# ICEDevice.net
KiCad netlist of a schematic drawn in EAGLE
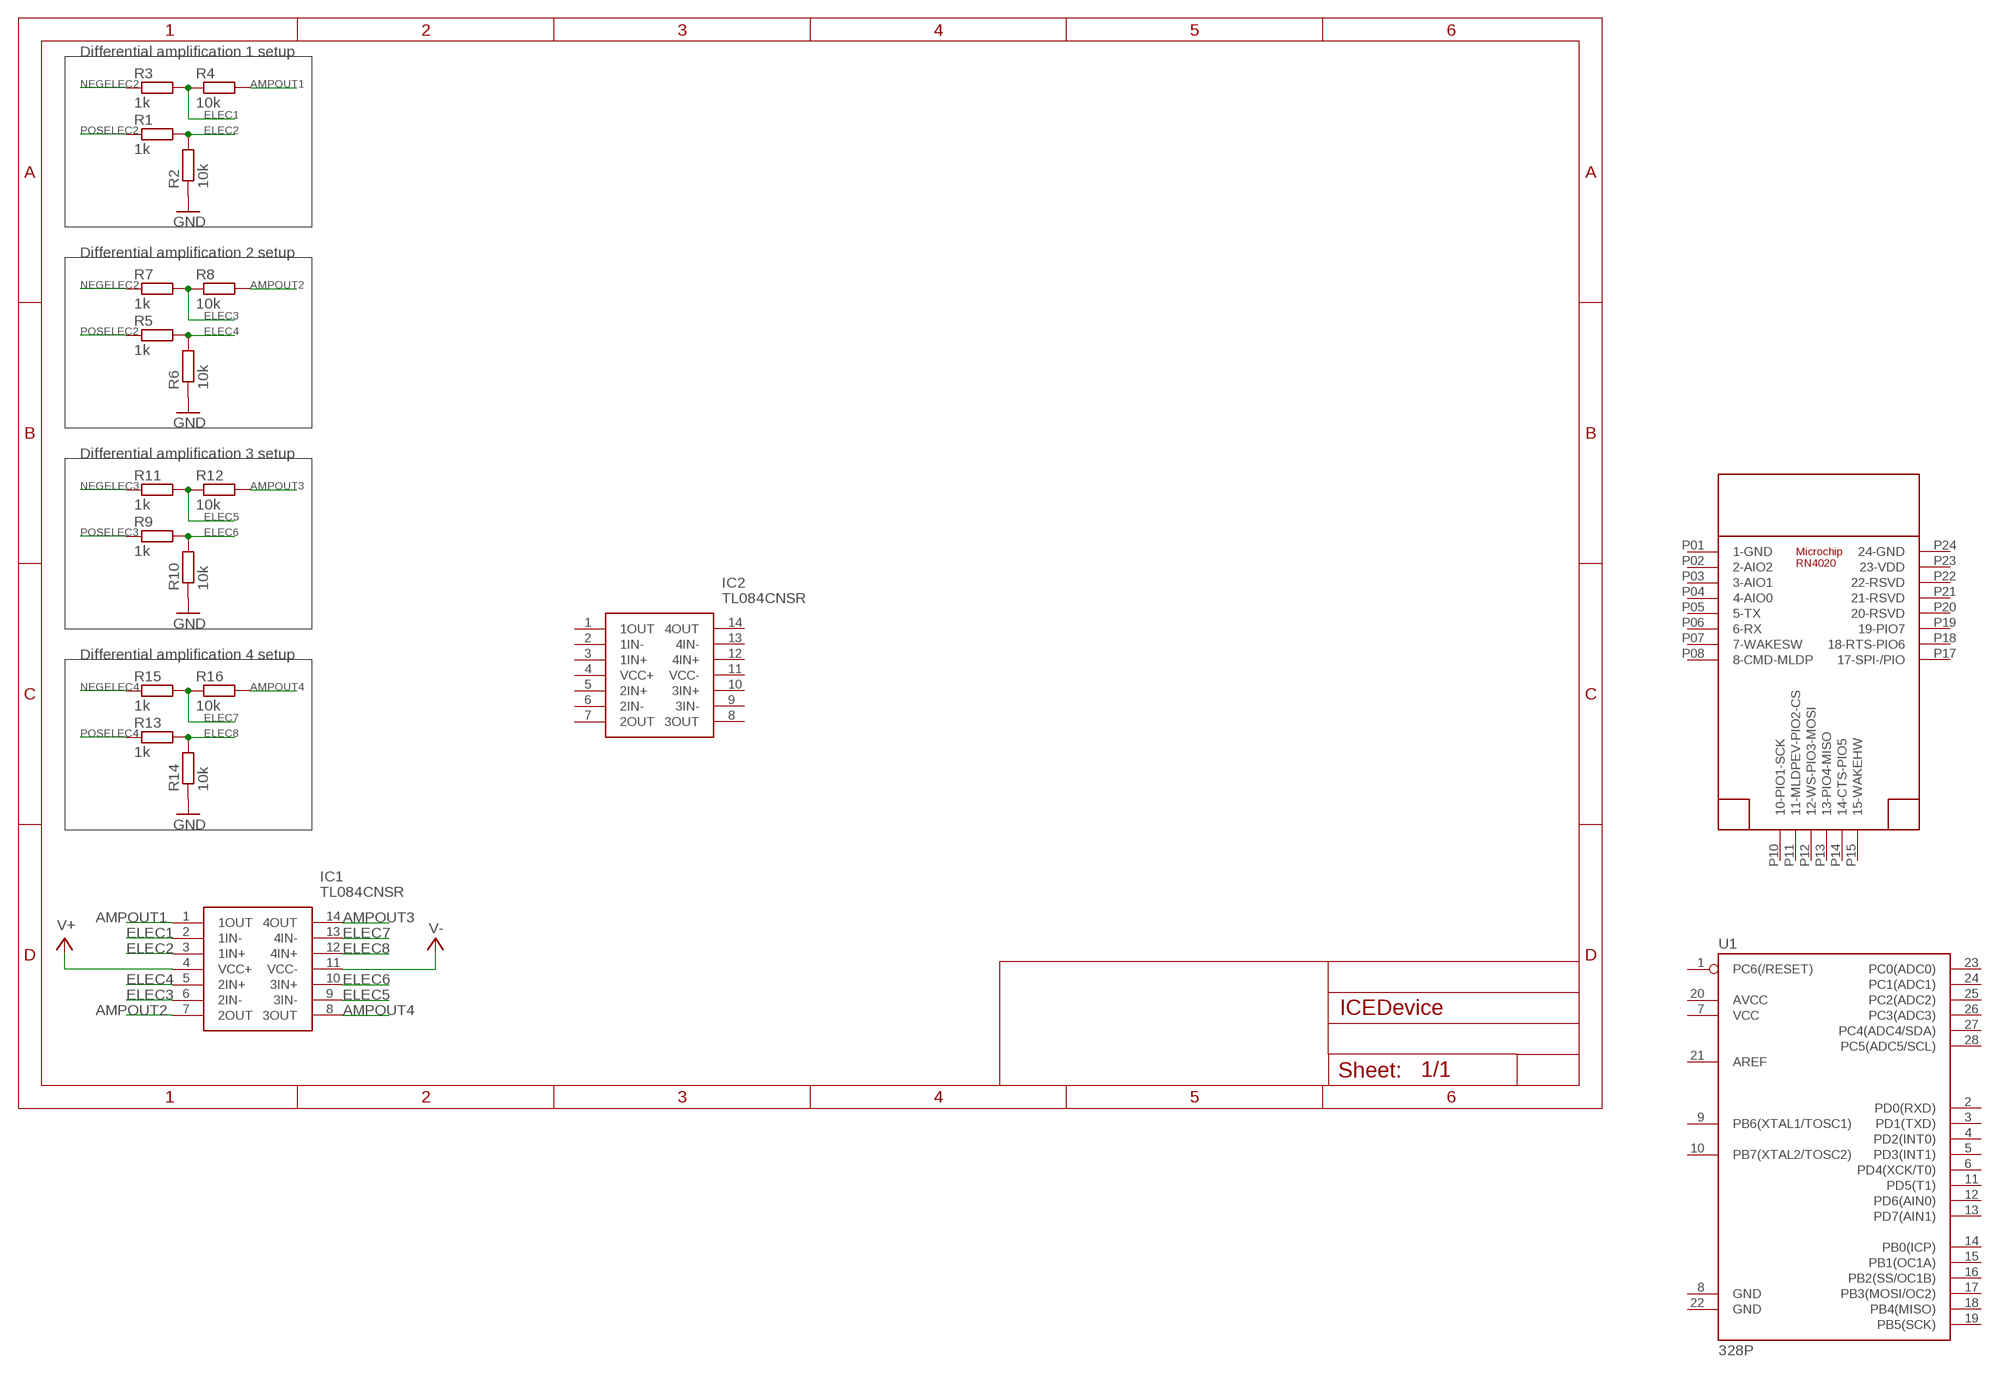
[diagram p0: schematic, sheet 1]

(export (version "E")
  (design (tool "Eeschema 10.0.6"))
  (components
    (comp (ref "IC1")
      (value "TL084CNSR")
      (footprint "eagle-import:SOIC127P780X200-14N")
      (fields (field (name "RS_PART_NUMBER") "1626742"))
      (libsource (lib "eagle-import") (part "TL084CNSR"))
    )
    (comp (ref "IC2")
      (value "TL084CNSR")
      (footprint "eagle-import:SOIC127P780X200-14N")
      (fields (field (name "RS_PART_NUMBER") "1626742"))
      (libsource (lib "eagle-import") (part "TL084CNSR"))
    )
    (comp (ref "R1")
      (value "1k")
      (footprint "eagle-import:0309_10")
      (libsource (lib "eagle-import") (part "R-EU_0309/10"))
    )
    (comp (ref "R2")
      (value "10k")
      (footprint "eagle-import:0309_10")
      (libsource (lib "eagle-import") (part "R-EU_0309/10"))
    )
    (comp (ref "R3")
      (value "1k")
      (footprint "eagle-import:0309_10")
      (libsource (lib "eagle-import") (part "R-EU_0309/10"))
    )
    (comp (ref "R4")
      (value "10k")
      (footprint "eagle-import:0309_10")
      (libsource (lib "eagle-import") (part "R-EU_0309/10"))
    )
    (comp (ref "R5")
      (value "1k")
      (footprint "eagle-import:0309_10")
      (libsource (lib "eagle-import") (part "R-EU_0309/10"))
    )
    (comp (ref "R6")
      (value "10k")
      (footprint "eagle-import:0309_10")
      (libsource (lib "eagle-import") (part "R-EU_0309/10"))
    )
    (comp (ref "R7")
      (value "1k")
      (footprint "eagle-import:0309_10")
      (libsource (lib "eagle-import") (part "R-EU_0309/10"))
    )
    (comp (ref "R8")
      (value "10k")
      (footprint "eagle-import:0309_10")
      (libsource (lib "eagle-import") (part "R-EU_0309/10"))
    )
    (comp (ref "R9")
      (value "1k")
      (footprint "eagle-import:0309_10")
      (libsource (lib "eagle-import") (part "R-EU_0309/10"))
    )
    (comp (ref "R10")
      (value "10k")
      (footprint "eagle-import:0309_10")
      (libsource (lib "eagle-import") (part "R-EU_0309/10"))
    )
    (comp (ref "R11")
      (value "1k")
      (footprint "eagle-import:0309_10")
      (libsource (lib "eagle-import") (part "R-EU_0309/10"))
    )
    (comp (ref "R12")
      (value "10k")
      (footprint "eagle-import:0309_10")
      (libsource (lib "eagle-import") (part "R-EU_0309/10"))
    )
    (comp (ref "R13")
      (value "1k")
      (footprint "eagle-import:0309_10")
      (libsource (lib "eagle-import") (part "R-EU_0309/10"))
    )
    (comp (ref "R14")
      (value "10k")
      (footprint "eagle-import:0309_10")
      (libsource (lib "eagle-import") (part "R-EU_0309/10"))
    )
    (comp (ref "R15")
      (value "1k")
      (footprint "eagle-import:0309_10")
      (libsource (lib "eagle-import") (part "R-EU_0309/10"))
    )
    (comp (ref "R16")
      (value "10k")
      (footprint "eagle-import:0309_10")
      (libsource (lib "eagle-import") (part "R-EU_0309/10"))
    )
    (comp (ref "U$1")
      (value "RN4020")
      (footprint "eagle-import:RN4020SMD")
      (libsource (lib "eagle-import") (part "RN4020"))
    )
    (comp (ref "U1")
      (value "328P")
      (footprint "eagle-import:DIP28")
      (libsource (lib "eagle-import") (part "ATMEGA328P_PDIP"))
    )
  )
  (nets
    (net (code "1") (name "/AMPOUT1") (class "Default")
      (node (ref "IC1") (pin "1") (pinfunction "1OUT_1") (pintype "bidirectional"))
      (node (ref "R4") (pin "2") (pinfunction "2_2") (pintype "passive"))
    )
    (net (code "2") (name "/AMPOUT2") (class "Default")
      (node (ref "IC1") (pin "7") (pinfunction "2OUT_7") (pintype "bidirectional"))
      (node (ref "R8") (pin "2") (pinfunction "2_2") (pintype "passive"))
    )
    (net (code "3") (name "/AMPOUT3") (class "Default")
      (node (ref "IC1") (pin "14") (pinfunction "4OUT_14") (pintype "bidirectional"))
      (node (ref "R12") (pin "2") (pinfunction "2_2") (pintype "passive"))
    )
    (net (code "4") (name "/AMPOUT4") (class "Default")
      (node (ref "IC1") (pin "8") (pinfunction "3OUT_8") (pintype "bidirectional"))
      (node (ref "R16") (pin "2") (pinfunction "2_2") (pintype "passive"))
    )
    (net (code "5") (name "/ELEC1") (class "Default")
      (node (ref "IC1") (pin "2") (pinfunction "1IN-_2") (pintype "bidirectional"))
      (node (ref "R3") (pin "2") (pinfunction "2_2") (pintype "passive"))
      (node (ref "R4") (pin "1") (pinfunction "1_1") (pintype "passive"))
    )
    (net (code "6") (name "/ELEC2") (class "Default")
      (node (ref "IC1") (pin "3") (pinfunction "1IN+_3") (pintype "bidirectional"))
      (node (ref "R1") (pin "2") (pinfunction "2_2") (pintype "passive"))
      (node (ref "R2") (pin "2") (pinfunction "2_2") (pintype "passive"))
    )
    (net (code "7") (name "/ELEC3") (class "Default")
      (node (ref "IC1") (pin "6") (pinfunction "2IN-_6") (pintype "bidirectional"))
      (node (ref "R7") (pin "2") (pinfunction "2_2") (pintype "passive"))
      (node (ref "R8") (pin "1") (pinfunction "1_1") (pintype "passive"))
    )
    (net (code "8") (name "/ELEC4") (class "Default")
      (node (ref "IC1") (pin "5") (pinfunction "2IN+_5") (pintype "bidirectional"))
      (node (ref "R5") (pin "2") (pinfunction "2_2") (pintype "passive"))
      (node (ref "R6") (pin "2") (pinfunction "2_2") (pintype "passive"))
    )
    (net (code "9") (name "/ELEC5") (class "Default")
      (node (ref "IC1") (pin "9") (pinfunction "3IN-_9") (pintype "bidirectional"))
      (node (ref "R11") (pin "2") (pinfunction "2_2") (pintype "passive"))
      (node (ref "R12") (pin "1") (pinfunction "1_1") (pintype "passive"))
    )
    (net (code "10") (name "/ELEC6") (class "Default")
      (node (ref "IC1") (pin "10") (pinfunction "3IN+_10") (pintype "bidirectional"))
      (node (ref "R10") (pin "2") (pinfunction "2_2") (pintype "passive"))
      (node (ref "R9") (pin "2") (pinfunction "2_2") (pintype "passive"))
    )
    (net (code "11") (name "/ELEC7") (class "Default")
      (node (ref "IC1") (pin "13") (pinfunction "4IN-_13") (pintype "bidirectional"))
      (node (ref "R15") (pin "2") (pinfunction "2_2") (pintype "passive"))
      (node (ref "R16") (pin "1") (pinfunction "1_1") (pintype "passive"))
    )
    (net (code "12") (name "/ELEC8") (class "Default")
      (node (ref "IC1") (pin "12") (pinfunction "4IN+_12") (pintype "bidirectional"))
      (node (ref "R13") (pin "2") (pinfunction "2_2") (pintype "passive"))
      (node (ref "R14") (pin "2") (pinfunction "2_2") (pintype "passive"))
    )
    (net (code "13") (name "/NEGELEC2") (class "Default")
      (node (ref "R3") (pin "1") (pinfunction "1_1") (pintype "passive"))
      (node (ref "R7") (pin "1") (pinfunction "1_1") (pintype "passive"))
    )
    (net (code "14") (name "/NEGELEC3") (class "Default")
      (node (ref "R11") (pin "1") (pinfunction "1_1") (pintype "passive"))
    )
    (net (code "15") (name "/NEGELEC4") (class "Default")
      (node (ref "R15") (pin "1") (pinfunction "1_1") (pintype "passive"))
    )
    (net (code "16") (name "/POSELEC2") (class "Default")
      (node (ref "R1") (pin "1") (pinfunction "1_1") (pintype "passive"))
      (node (ref "R5") (pin "1") (pinfunction "1_1") (pintype "passive"))
    )
    (net (code "17") (name "/POSELEC3") (class "Default")
      (node (ref "R9") (pin "1") (pinfunction "1_1") (pintype "passive"))
    )
    (net (code "18") (name "/POSELEC4") (class "Default")
      (node (ref "R13") (pin "1") (pinfunction "1_1") (pintype "passive"))
    )
    (net (code "19") (name "GND") (class "Default")
      (node (ref "R10") (pin "1") (pinfunction "1_1") (pintype "passive"))
      (node (ref "R14") (pin "1") (pinfunction "1_1") (pintype "passive"))
      (node (ref "R2") (pin "1") (pinfunction "1_1") (pintype "passive"))
      (node (ref "R6") (pin "1") (pinfunction "1_1") (pintype "passive"))
    )
    (net (code "20") (name "V+") (class "Default")
      (node (ref "IC1") (pin "4") (pinfunction "VCC+_4") (pintype "bidirectional"))
    )
    (net (code "21") (name "V-") (class "Default")
      (node (ref "IC1") (pin "11") (pinfunction "VCC-_11") (pintype "bidirectional"))
    )
    (net (code "22") (name "unconnected-(IC2-1IN+-Pad3)") (class "Default")
      (node (ref "IC2") (pin "3") (pinfunction "1IN+_3") (pintype "bidirectional"))
    )
    (net (code "23") (name "unconnected-(IC2-1IN--Pad2)") (class "Default")
      (node (ref "IC2") (pin "2") (pinfunction "1IN-_2") (pintype "bidirectional"))
    )
    (net (code "24") (name "unconnected-(IC2-1OUT-Pad1)") (class "Default")
      (node (ref "IC2") (pin "1") (pinfunction "1OUT_1") (pintype "bidirectional"))
    )
    (net (code "25") (name "unconnected-(IC2-2IN+-Pad5)") (class "Default")
      (node (ref "IC2") (pin "5") (pinfunction "2IN+_5") (pintype "bidirectional"))
    )
    (net (code "26") (name "unconnected-(IC2-2IN--Pad6)") (class "Default")
      (node (ref "IC2") (pin "6") (pinfunction "2IN-_6") (pintype "bidirectional"))
    )
    (net (code "27") (name "unconnected-(IC2-2OUT-Pad7)") (class "Default")
      (node (ref "IC2") (pin "7") (pinfunction "2OUT_7") (pintype "bidirectional"))
    )
    (net (code "28") (name "unconnected-(IC2-3IN+-Pad10)") (class "Default")
      (node (ref "IC2") (pin "10") (pinfunction "3IN+_10") (pintype "bidirectional"))
    )
    (net (code "29") (name "unconnected-(IC2-3IN--Pad9)") (class "Default")
      (node (ref "IC2") (pin "9") (pinfunction "3IN-_9") (pintype "bidirectional"))
    )
    (net (code "30") (name "unconnected-(IC2-3OUT-Pad8)") (class "Default")
      (node (ref "IC2") (pin "8") (pinfunction "3OUT_8") (pintype "bidirectional"))
    )
    (net (code "31") (name "unconnected-(IC2-4IN+-Pad12)") (class "Default")
      (node (ref "IC2") (pin "12") (pinfunction "4IN+_12") (pintype "bidirectional"))
    )
    (net (code "32") (name "unconnected-(IC2-4IN--Pad13)") (class "Default")
      (node (ref "IC2") (pin "13") (pinfunction "4IN-_13") (pintype "bidirectional"))
    )
    (net (code "33") (name "unconnected-(IC2-4OUT-Pad14)") (class "Default")
      (node (ref "IC2") (pin "14") (pinfunction "4OUT_14") (pintype "bidirectional"))
    )
    (net (code "34") (name "unconnected-(IC2-VCC+-Pad4)") (class "Default")
      (node (ref "IC2") (pin "4") (pinfunction "VCC+_4") (pintype "bidirectional"))
    )
    (net (code "35") (name "unconnected-(IC2-VCC--Pad11)") (class "Default")
      (node (ref "IC2") (pin "11") (pinfunction "VCC-_11") (pintype "bidirectional"))
    )
    (net (code "36") (name "unconnected-(U$1-1-GND-PadP01)") (class "Default")
      (node (ref "U$1") (pin "P01") (pinfunction "1-GND_P01") (pintype "bidirectional"))
    )
    (net (code "37") (name "unconnected-(U$1-2-AIO2-PadP02)") (class "Default")
      (node (ref "U$1") (pin "P02") (pinfunction "2-AIO2_P02") (pintype "bidirectional"))
    )
    (net (code "38") (name "unconnected-(U$1-3-AIO1-PadP03)") (class "Default")
      (node (ref "U$1") (pin "P03") (pinfunction "3-AIO1_P03") (pintype "bidirectional"))
    )
    (net (code "39") (name "unconnected-(U$1-4-AIO0-PadP04)") (class "Default")
      (node (ref "U$1") (pin "P04") (pinfunction "4-AIO0_P04") (pintype "bidirectional"))
    )
    (net (code "40") (name "unconnected-(U$1-5-TX-PadP05)") (class "Default")
      (node (ref "U$1") (pin "P05") (pinfunction "5-TX_P05") (pintype "bidirectional"))
    )
    (net (code "41") (name "unconnected-(U$1-6-RX-PadP06)") (class "Default")
      (node (ref "U$1") (pin "P06") (pinfunction "6-RX_P06") (pintype "bidirectional"))
    )
    (net (code "42") (name "unconnected-(U$1-7-WAKESW-PadP07)") (class "Default")
      (node (ref "U$1") (pin "P07") (pinfunction "7-WAKESW_P07") (pintype "bidirectional"))
    )
    (net (code "43") (name "unconnected-(U$1-8-CMD-MLDP-PadP08)") (class "Default")
      (node (ref "U$1") (pin "P08") (pinfunction "8-CMD-MLDP_P08") (pintype "bidirectional"))
    )
    (net (code "44") (name "unconnected-(U$1-10-PIO1-SCK-PadP10)") (class "Default")
      (node (ref "U$1") (pin "P10") (pinfunction "10-PIO1-SCK_P10") (pintype "bidirectional"))
    )
    (net (code "45") (name "unconnected-(U$1-11-MLDPEV-PIO2-CS-PadP11)") (class "Default")
      (node (ref "U$1") (pin "P11") (pinfunction "11-MLDPEV-PIO2-CS_P11") (pintype "bidirectional"))
    )
    (net (code "46") (name "unconnected-(U$1-12-WS-PIO3-MOSI-PadP12)") (class "Default")
      (node (ref "U$1") (pin "P12") (pinfunction "12-WS-PIO3-MOSI_P12") (pintype "bidirectional"))
    )
    (net (code "47") (name "unconnected-(U$1-13-PIO4-MISO-PadP13)") (class "Default")
      (node (ref "U$1") (pin "P13") (pinfunction "13-PIO4-MISO_P13") (pintype "bidirectional"))
    )
    (net (code "48") (name "unconnected-(U$1-14-CTS-PIO5-PadP14)") (class "Default")
      (node (ref "U$1") (pin "P14") (pinfunction "14-CTS-PIO5_P14") (pintype "bidirectional"))
    )
    (net (code "49") (name "unconnected-(U$1-15-WAKEHW-PadP15)") (class "Default")
      (node (ref "U$1") (pin "P15") (pinfunction "15-WAKEHW_P15") (pintype "bidirectional"))
    )
    (net (code "50") (name "unconnected-(U$1-17-SPI-{slash}PIO-PadP17)") (class "Default")
      (node (ref "U$1") (pin "P17") (pinfunction "17-SPI-/PIO_P17") (pintype "bidirectional"))
    )
    (net (code "51") (name "unconnected-(U$1-18-RTS-PIO6-PadP18)") (class "Default")
      (node (ref "U$1") (pin "P18") (pinfunction "18-RTS-PIO6_P18") (pintype "bidirectional"))
    )
    (net (code "52") (name "unconnected-(U$1-19-PIO7-PadP19)") (class "Default")
      (node (ref "U$1") (pin "P19") (pinfunction "19-PIO7_P19") (pintype "bidirectional"))
    )
    (net (code "53") (name "unconnected-(U$1-20-RSVD-PadP20)") (class "Default")
      (node (ref "U$1") (pin "P20") (pinfunction "20-RSVD_P20") (pintype "bidirectional"))
    )
    (net (code "54") (name "unconnected-(U$1-21-RSVD-PadP21)") (class "Default")
      (node (ref "U$1") (pin "P21") (pinfunction "21-RSVD_P21") (pintype "bidirectional"))
    )
    (net (code "55") (name "unconnected-(U$1-22-RSVD-PadP22)") (class "Default")
      (node (ref "U$1") (pin "P22") (pinfunction "22-RSVD_P22") (pintype "bidirectional"))
    )
    (net (code "56") (name "unconnected-(U$1-23-VDD-PadP23)") (class "Default")
      (node (ref "U$1") (pin "P23") (pinfunction "23-VDD_P23") (pintype "bidirectional"))
    )
    (net (code "57") (name "unconnected-(U$1-24-GND-PadP24)") (class "Default")
      (node (ref "U$1") (pin "P24") (pinfunction "24-GND_P24") (pintype "bidirectional"))
    )
    (net (code "58") (name "unconnected-(U1-AREF-Pad21)") (class "Default")
      (node (ref "U1") (pin "21") (pinfunction "AREF_21") (pintype "bidirectional"))
    )
    (net (code "59") (name "unconnected-(U1-AVCC-Pad20)") (class "Default")
      (node (ref "U1") (pin "20") (pinfunction "AVCC_20") (pintype "bidirectional"))
    )
    (net (code "60") (name "unconnected-(U1-GND-Pad8)") (class "Default")
      (node (ref "U1") (pin "8") (pinfunction "GND_8") (pintype "bidirectional"))
    )
    (net (code "61") (name "unconnected-(U1-GND-Pad22)") (class "Default")
      (node (ref "U1") (pin "22") (pinfunction "GND_22") (pintype "bidirectional"))
    )
    (net (code "62") (name "unconnected-(U1-PB0(ICP)-Pad14)") (class "Default")
      (node (ref "U1") (pin "14") (pinfunction "PB0(ICP)_14") (pintype "bidirectional"))
    )
    (net (code "63") (name "unconnected-(U1-PB1(OC1A)-Pad15)") (class "Default")
      (node (ref "U1") (pin "15") (pinfunction "PB1(OC1A)_15") (pintype "bidirectional"))
    )
    (net (code "64") (name "unconnected-(U1-PB2(SS{slash}OC1B)-Pad16)") (class "Default")
      (node (ref "U1") (pin "16") (pinfunction "PB2(SS/OC1B)_16") (pintype "bidirectional"))
    )
    (net (code "65") (name "unconnected-(U1-PB3(MOSI{slash}OC2)-Pad17)") (class "Default")
      (node (ref "U1") (pin "17") (pinfunction "PB3(MOSI/OC2)_17") (pintype "bidirectional"))
    )
    (net (code "66") (name "unconnected-(U1-PB4(MISO)-Pad18)") (class "Default")
      (node (ref "U1") (pin "18") (pinfunction "PB4(MISO)_18") (pintype "bidirectional"))
    )
    (net (code "67") (name "unconnected-(U1-PB5(SCK)-Pad19)") (class "Default")
      (node (ref "U1") (pin "19") (pinfunction "PB5(SCK)_19") (pintype "bidirectional"))
    )
    (net (code "68") (name "unconnected-(U1-PB6(XTAL1{slash}TOSC1)-Pad9)") (class "Default")
      (node (ref "U1") (pin "9") (pinfunction "PB6(XTAL1/TOSC1)_9") (pintype "bidirectional"))
    )
    (net (code "69") (name "unconnected-(U1-PB7(XTAL2{slash}TOSC2)-Pad10)") (class "Default")
      (node (ref "U1") (pin "10") (pinfunction "PB7(XTAL2/TOSC2)_10") (pintype "bidirectional"))
    )
    (net (code "70") (name "unconnected-(U1-PC0(ADC0)-Pad23)") (class "Default")
      (node (ref "U1") (pin "23") (pinfunction "PC0(ADC0)_23") (pintype "bidirectional"))
    )
    (net (code "71") (name "unconnected-(U1-PC1(ADC1)-Pad24)") (class "Default")
      (node (ref "U1") (pin "24") (pinfunction "PC1(ADC1)_24") (pintype "bidirectional"))
    )
    (net (code "72") (name "unconnected-(U1-PC2(ADC2)-Pad25)") (class "Default")
      (node (ref "U1") (pin "25") (pinfunction "PC2(ADC2)_25") (pintype "bidirectional"))
    )
    (net (code "73") (name "unconnected-(U1-PC3(ADC3)-Pad26)") (class "Default")
      (node (ref "U1") (pin "26") (pinfunction "PC3(ADC3)_26") (pintype "bidirectional"))
    )
    (net (code "74") (name "unconnected-(U1-PC4(ADC4{slash}SDA)-Pad27)") (class "Default")
      (node (ref "U1") (pin "27") (pinfunction "PC4(ADC4/SDA)_27") (pintype "bidirectional"))
    )
    (net (code "75") (name "unconnected-(U1-PC5(ADC5{slash}SCL)-Pad28)") (class "Default")
      (node (ref "U1") (pin "28") (pinfunction "PC5(ADC5/SCL)_28") (pintype "bidirectional"))
    )
    (net (code "76") (name "unconnected-(U1-PC6({slash}RESET)-Pad1)") (class "Default")
      (node (ref "U1") (pin "1") (pinfunction "PC6(/RESET)_1") (pintype "bidirectional"))
    )
    (net (code "77") (name "unconnected-(U1-PD0(RXD)-Pad2)") (class "Default")
      (node (ref "U1") (pin "2") (pinfunction "PD0(RXD)_2") (pintype "bidirectional"))
    )
    (net (code "78") (name "unconnected-(U1-PD1(TXD)-Pad3)") (class "Default")
      (node (ref "U1") (pin "3") (pinfunction "PD1(TXD)_3") (pintype "bidirectional"))
    )
    (net (code "79") (name "unconnected-(U1-PD2(INT0)-Pad4)") (class "Default")
      (node (ref "U1") (pin "4") (pinfunction "PD2(INT0)_4") (pintype "bidirectional"))
    )
    (net (code "80") (name "unconnected-(U1-PD3(INT1)-Pad5)") (class "Default")
      (node (ref "U1") (pin "5") (pinfunction "PD3(INT1)_5") (pintype "bidirectional"))
    )
    (net (code "81") (name "unconnected-(U1-PD4(XCK{slash}T0)-Pad6)") (class "Default")
      (node (ref "U1") (pin "6") (pinfunction "PD4(XCK/T0)_6") (pintype "bidirectional"))
    )
    (net (code "82") (name "unconnected-(U1-PD5(T1)-Pad11)") (class "Default")
      (node (ref "U1") (pin "11") (pinfunction "PD5(T1)_11") (pintype "bidirectional"))
    )
    (net (code "83") (name "unconnected-(U1-PD6(AIN0)-Pad12)") (class "Default")
      (node (ref "U1") (pin "12") (pinfunction "PD6(AIN0)_12") (pintype "bidirectional"))
    )
    (net (code "84") (name "unconnected-(U1-PD7(AIN1)-Pad13)") (class "Default")
      (node (ref "U1") (pin "13") (pinfunction "PD7(AIN1)_13") (pintype "bidirectional"))
    )
    (net (code "85") (name "unconnected-(U1-VCC-Pad7)") (class "Default")
      (node (ref "U1") (pin "7") (pinfunction "VCC_7") (pintype "bidirectional"))
    )
  )
)
